# SCH_ledAndButonMcp23017_2023-08-30.net
KiCad netlist of a schematic drawn in EasyEDA
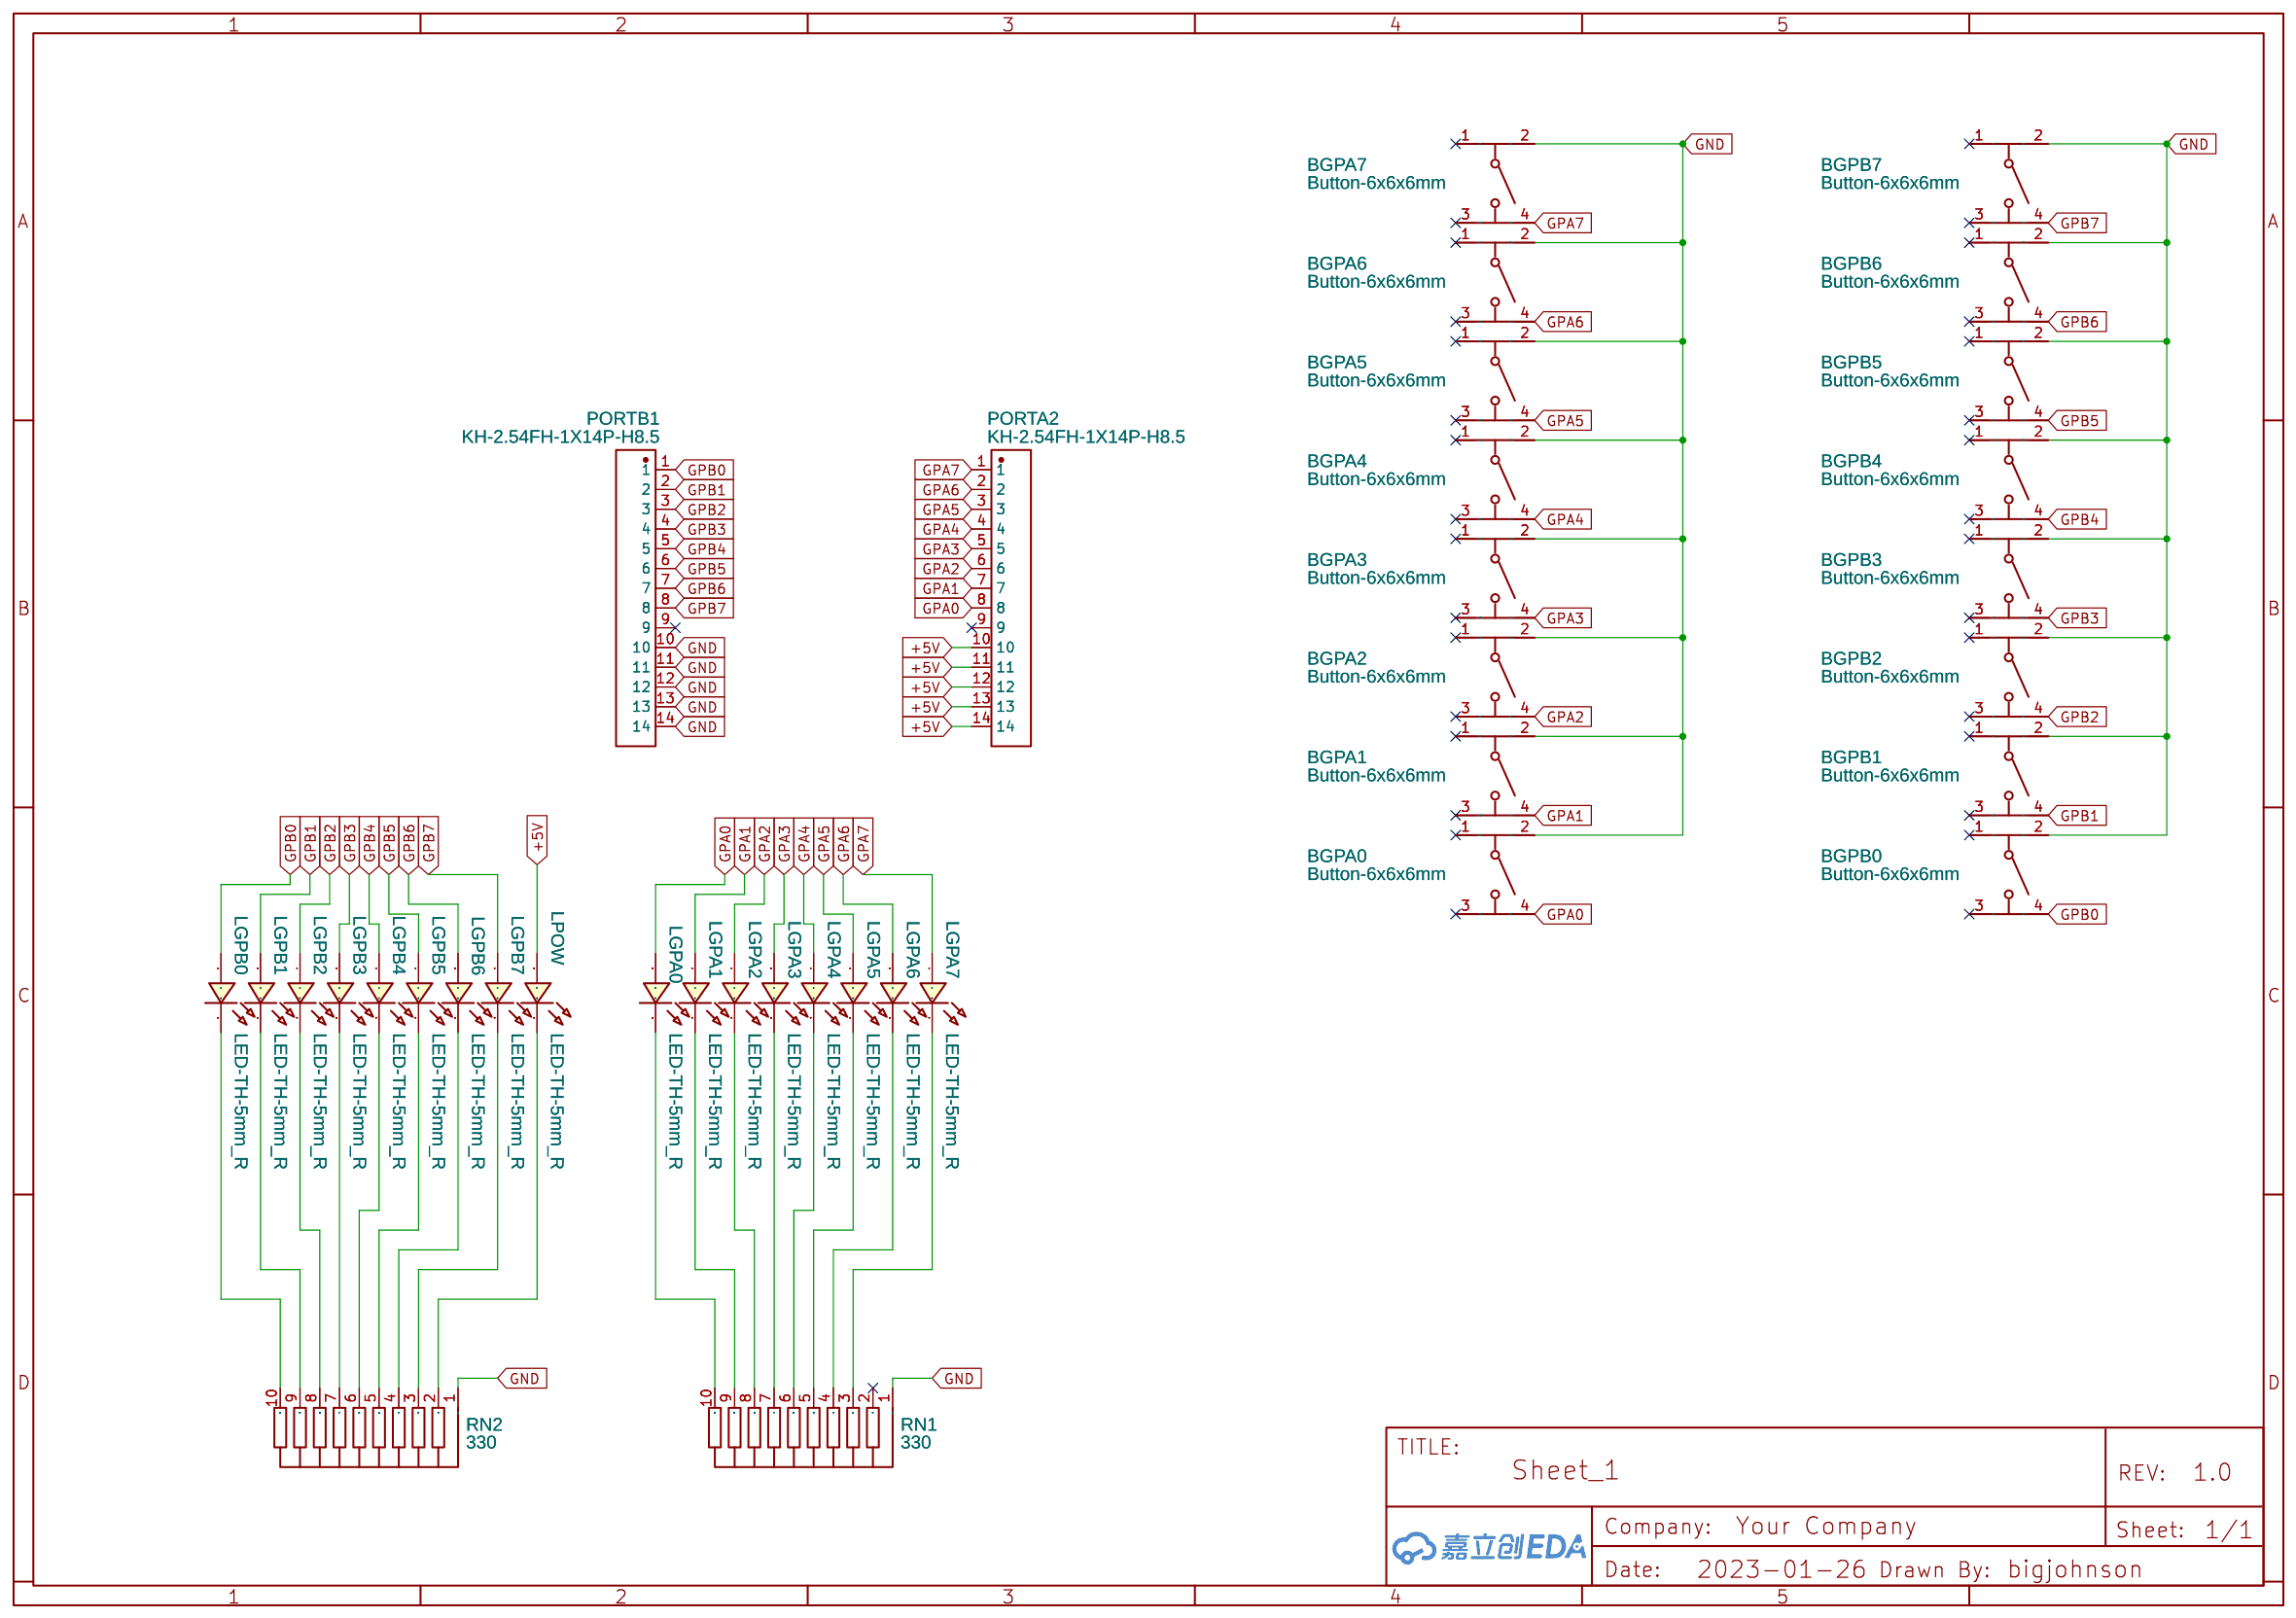
[diagram p0: schematic sheet]

(export (version "E")
  (design (tool "Eeschema 10.0.6"))
  (components
    (comp (ref "BGPA0")
      (value "Button-6x6x6mm")
      (fields
        (field (name "Manufacturer Part") "Switch,6*6*6Plastic head,260G, 0.25mm,Straight line")
        (field (name "Manufacturer") "BBJ")
      )
      (libsource (lib "") (part "Button-6x6x6mm_1"))
    )
    (comp (ref "BGPA1")
      (value "Button-6x6x6mm")
      (fields
        (field (name "Manufacturer Part") "Switch,6*6*6Plastic head,260G, 0.25mm,Straight line")
        (field (name "Manufacturer") "BBJ")
      )
      (libsource (lib "") (part "Button-6x6x6mm_1"))
    )
    (comp (ref "BGPA2")
      (value "Button-6x6x6mm")
      (fields
        (field (name "Manufacturer Part") "Switch,6*6*6Plastic head,260G, 0.25mm,Straight line")
        (field (name "Manufacturer") "BBJ")
      )
      (libsource (lib "") (part "Button-6x6x6mm_1"))
    )
    (comp (ref "BGPA3")
      (value "Button-6x6x6mm")
      (fields
        (field (name "Manufacturer Part") "Switch,6*6*6Plastic head,260G, 0.25mm,Straight line")
        (field (name "Manufacturer") "BBJ")
      )
      (libsource (lib "") (part "Button-6x6x6mm_1"))
    )
    (comp (ref "BGPA4")
      (value "Button-6x6x6mm")
      (fields
        (field (name "Manufacturer Part") "Switch,6*6*6Plastic head,260G, 0.25mm,Straight line")
        (field (name "Manufacturer") "BBJ")
      )
      (libsource (lib "") (part "Button-6x6x6mm_1"))
    )
    (comp (ref "BGPA5")
      (value "Button-6x6x6mm")
      (fields
        (field (name "Manufacturer Part") "Switch,6*6*6Plastic head,260G, 0.25mm,Straight line")
        (field (name "Manufacturer") "BBJ")
      )
      (libsource (lib "") (part "Button-6x6x6mm_1"))
    )
    (comp (ref "BGPA6")
      (value "Button-6x6x6mm")
      (fields
        (field (name "Manufacturer Part") "Switch,6*6*6Plastic head,260G, 0.25mm,Straight line")
        (field (name "Manufacturer") "BBJ")
      )
      (libsource (lib "") (part "Button-6x6x6mm_1"))
    )
    (comp (ref "BGPA7")
      (value "Button-6x6x6mm")
      (fields
        (field (name "Manufacturer Part") "Switch,6*6*6Plastic head,260G, 0.25mm,Straight line")
        (field (name "Manufacturer") "BBJ")
      )
      (libsource (lib "") (part "Button-6x6x6mm_1"))
    )
    (comp (ref "BGPB0")
      (value "Button-6x6x6mm")
      (fields
        (field (name "Manufacturer Part") "Switch,6*6*6Plastic head,260G, 0.25mm,Straight line")
        (field (name "Manufacturer") "BBJ")
      )
      (libsource (lib "") (part "Button-6x6x6mm"))
    )
    (comp (ref "BGPB1")
      (value "Button-6x6x6mm")
      (fields
        (field (name "Manufacturer Part") "Switch,6*6*6Plastic head,260G, 0.25mm,Straight line")
        (field (name "Manufacturer") "BBJ")
      )
      (libsource (lib "") (part "Button-6x6x6mm"))
    )
    (comp (ref "BGPB2")
      (value "Button-6x6x6mm")
      (fields
        (field (name "Manufacturer Part") "Switch,6*6*6Plastic head,260G, 0.25mm,Straight line")
        (field (name "Manufacturer") "BBJ")
      )
      (libsource (lib "") (part "Button-6x6x6mm"))
    )
    (comp (ref "BGPB3")
      (value "Button-6x6x6mm")
      (fields
        (field (name "Manufacturer Part") "Switch,6*6*6Plastic head,260G, 0.25mm,Straight line")
        (field (name "Manufacturer") "BBJ")
      )
      (libsource (lib "") (part "Button-6x6x6mm"))
    )
    (comp (ref "BGPB4")
      (value "Button-6x6x6mm")
      (fields
        (field (name "Manufacturer Part") "Switch,6*6*6Plastic head,260G, 0.25mm,Straight line")
        (field (name "Manufacturer") "BBJ")
      )
      (libsource (lib "") (part "Button-6x6x6mm"))
    )
    (comp (ref "BGPB5")
      (value "Button-6x6x6mm")
      (fields
        (field (name "Manufacturer Part") "Switch,6*6*6Plastic head,260G, 0.25mm,Straight line")
        (field (name "Manufacturer") "BBJ")
      )
      (libsource (lib "") (part "Button-6x6x6mm"))
    )
    (comp (ref "BGPB6")
      (value "Button-6x6x6mm")
      (fields
        (field (name "Manufacturer Part") "Switch,6*6*6Plastic head,260G, 0.25mm,Straight line")
        (field (name "Manufacturer") "BBJ")
      )
      (libsource (lib "") (part "Button-6x6x6mm"))
    )
    (comp (ref "BGPB7")
      (value "Button-6x6x6mm")
      (fields
        (field (name "Manufacturer Part") "Switch,6*6*6Plastic head,260G, 0.25mm,Straight line")
        (field (name "Manufacturer") "BBJ")
      )
      (libsource (lib "") (part "Button-6x6x6mm"))
    )
    (comp (ref "LGPA0")
      (value "LED-TH-5mm_R")
      (fields
        (field (name "Manufacturer Part") "333-2SURD/S530-A3")
        (field (name "Manufacturer") "EVERLIGHT(台湾亿光)")
      )
      (libsource (lib "") (part "LED-TH-5mm_R"))
    )
    (comp (ref "LGPA1")
      (value "LED-TH-5mm_R")
      (fields
        (field (name "Manufacturer Part") "333-2SURD/S530-A3")
        (field (name "Manufacturer") "EVERLIGHT(台湾亿光)")
      )
      (libsource (lib "") (part "LED-TH-5mm_R"))
    )
    (comp (ref "LGPA2")
      (value "LED-TH-5mm_R")
      (fields
        (field (name "Manufacturer Part") "333-2SURD/S530-A3")
        (field (name "Manufacturer") "EVERLIGHT(台湾亿光)")
      )
      (libsource (lib "") (part "LED-TH-5mm_R"))
    )
    (comp (ref "LGPA3")
      (value "LED-TH-5mm_R")
      (fields
        (field (name "Manufacturer Part") "333-2SURD/S530-A3")
        (field (name "Manufacturer") "EVERLIGHT(台湾亿光)")
      )
      (libsource (lib "") (part "LED-TH-5mm_R"))
    )
    (comp (ref "LGPA4")
      (value "LED-TH-5mm_R")
      (fields
        (field (name "Manufacturer Part") "333-2SURD/S530-A3")
        (field (name "Manufacturer") "EVERLIGHT(台湾亿光)")
      )
      (libsource (lib "") (part "LED-TH-5mm_R"))
    )
    (comp (ref "LGPA5")
      (value "LED-TH-5mm_R")
      (fields
        (field (name "Manufacturer Part") "333-2SURD/S530-A3")
        (field (name "Manufacturer") "EVERLIGHT(台湾亿光)")
      )
      (libsource (lib "") (part "LED-TH-5mm_R"))
    )
    (comp (ref "LGPA6")
      (value "LED-TH-5mm_R")
      (fields
        (field (name "Manufacturer Part") "333-2SURD/S530-A3")
        (field (name "Manufacturer") "EVERLIGHT(台湾亿光)")
      )
      (libsource (lib "") (part "LED-TH-5mm_R"))
    )
    (comp (ref "LGPA7")
      (value "LED-TH-5mm_R")
      (fields
        (field (name "Manufacturer Part") "333-2SURD/S530-A3")
        (field (name "Manufacturer") "EVERLIGHT(台湾亿光)")
      )
      (libsource (lib "") (part "LED-TH-5mm_R"))
    )
    (comp (ref "LGPB0")
      (value "LED-TH-5mm_R")
      (fields
        (field (name "Manufacturer Part") "333-2SURD/S530-A3")
        (field (name "Manufacturer") "EVERLIGHT(台湾亿光)")
      )
      (libsource (lib "") (part "LED-TH-5mm_R_1"))
    )
    (comp (ref "LGPB1")
      (value "LED-TH-5mm_R")
      (fields
        (field (name "Manufacturer Part") "333-2SURD/S530-A3")
        (field (name "Manufacturer") "EVERLIGHT(台湾亿光)")
      )
      (libsource (lib "") (part "LED-TH-5mm_R_1"))
    )
    (comp (ref "LGPB2")
      (value "LED-TH-5mm_R")
      (fields
        (field (name "Manufacturer Part") "333-2SURD/S530-A3")
        (field (name "Manufacturer") "EVERLIGHT(台湾亿光)")
      )
      (libsource (lib "") (part "LED-TH-5mm_R_1"))
    )
    (comp (ref "LGPB3")
      (value "LED-TH-5mm_R")
      (fields
        (field (name "Manufacturer Part") "333-2SURD/S530-A3")
        (field (name "Manufacturer") "EVERLIGHT(台湾亿光)")
      )
      (libsource (lib "") (part "LED-TH-5mm_R_1"))
    )
    (comp (ref "LGPB4")
      (value "LED-TH-5mm_R")
      (fields
        (field (name "Manufacturer Part") "333-2SURD/S530-A3")
        (field (name "Manufacturer") "EVERLIGHT(台湾亿光)")
      )
      (libsource (lib "") (part "LED-TH-5mm_R_1"))
    )
    (comp (ref "LGPB5")
      (value "LED-TH-5mm_R")
      (fields
        (field (name "Manufacturer Part") "333-2SURD/S530-A3")
        (field (name "Manufacturer") "EVERLIGHT(台湾亿光)")
      )
      (libsource (lib "") (part "LED-TH-5mm_R_1"))
    )
    (comp (ref "LGPB6")
      (value "LED-TH-5mm_R")
      (fields
        (field (name "Manufacturer Part") "333-2SURD/S530-A3")
        (field (name "Manufacturer") "EVERLIGHT(台湾亿光)")
      )
      (libsource (lib "") (part "LED-TH-5mm_R_1"))
    )
    (comp (ref "LGPB7")
      (value "LED-TH-5mm_R")
      (fields
        (field (name "Manufacturer Part") "333-2SURD/S530-A3")
        (field (name "Manufacturer") "EVERLIGHT(台湾亿光)")
      )
      (libsource (lib "") (part "LED-TH-5mm_R_1"))
    )
    (comp (ref "LPOW")
      (value "LED-TH-5mm_R")
      (fields
        (field (name "Manufacturer Part") "333-2SURD/S530-A3")
        (field (name "Manufacturer") "EVERLIGHT(台湾亿光)")
      )
      (libsource (lib "") (part "LED-TH-5mm_R_2"))
    )
    (comp (ref "PORTA2")
      (value "KH-2.54FH-1X14P-H8.5")
      (fields (field (name "Manufacturer") "kinghelm(金航标)"))
      (libsource (lib "") (part "KH-2.54FH-1X14P-H8.5_1"))
    )
    (comp (ref "PORTB1")
      (value "KH-2.54FH-1X14P-H8.5")
      (fields (field (name "Manufacturer") "kinghelm(金航标)"))
      (libsource (lib "") (part "KH-2.54FH-1X14P-H8.5"))
    )
    (comp (ref "RN1")
      (value "330")
      (fields
        (field (name "Manufacturer Part") "RAA10103G")
        (field (name "Manufacturer") "ZHUHAI MONEC ELEC")
      )
      (libsource (lib "") (part "RAA10103G"))
    )
    (comp (ref "RN2")
      (value "330")
      (fields
        (field (name "Manufacturer Part") "RAA10103G")
        (field (name "Manufacturer") "ZHUHAI MONEC ELEC")
      )
      (libsource (lib "") (part "RAA10103G"))
    )
  )
  (nets
    (net (code "1") (name "+5V") (class "Default")
      (node (ref "LPOW") (pin "1") (pinfunction "1_1") (pintype "unspecified"))
      (node (ref "PORTA2") (pin "10") (pinfunction "10_10") (pintype "unspecified"))
      (node (ref "PORTA2") (pin "11") (pinfunction "11_11") (pintype "unspecified"))
      (node (ref "PORTA2") (pin "12") (pinfunction "12_12") (pintype "unspecified"))
      (node (ref "PORTA2") (pin "13") (pinfunction "13_13") (pintype "unspecified"))
      (node (ref "PORTA2") (pin "14") (pinfunction "14_14") (pintype "unspecified"))
    )
    (net (code "2") (name "GND") (class "Default")
      (node (ref "BGPA0") (pin "2") (pinfunction "2_2") (pintype "unspecified"))
      (node (ref "BGPA1") (pin "2") (pinfunction "2_2") (pintype "unspecified"))
      (node (ref "BGPA2") (pin "2") (pinfunction "2_2") (pintype "unspecified"))
      (node (ref "BGPA3") (pin "2") (pinfunction "2_2") (pintype "unspecified"))
      (node (ref "BGPA4") (pin "2") (pinfunction "2_2") (pintype "unspecified"))
      (node (ref "BGPA5") (pin "2") (pinfunction "2_2") (pintype "unspecified"))
      (node (ref "BGPA6") (pin "2") (pinfunction "2_2") (pintype "unspecified"))
      (node (ref "BGPA7") (pin "2") (pinfunction "2_2") (pintype "unspecified"))
      (node (ref "BGPB0") (pin "2") (pinfunction "2_2") (pintype "unspecified"))
      (node (ref "BGPB1") (pin "2") (pinfunction "2_2") (pintype "unspecified"))
      (node (ref "BGPB2") (pin "2") (pinfunction "2_2") (pintype "unspecified"))
      (node (ref "BGPB3") (pin "2") (pinfunction "2_2") (pintype "unspecified"))
      (node (ref "BGPB4") (pin "2") (pinfunction "2_2") (pintype "unspecified"))
      (node (ref "BGPB5") (pin "2") (pinfunction "2_2") (pintype "unspecified"))
      (node (ref "BGPB6") (pin "2") (pinfunction "2_2") (pintype "unspecified"))
      (node (ref "BGPB7") (pin "2") (pinfunction "2_2") (pintype "unspecified"))
      (node (ref "PORTB1") (pin "10") (pinfunction "10_10") (pintype "unspecified"))
      (node (ref "PORTB1") (pin "11") (pinfunction "11_11") (pintype "unspecified"))
      (node (ref "PORTB1") (pin "12") (pinfunction "12_12") (pintype "unspecified"))
      (node (ref "PORTB1") (pin "13") (pinfunction "13_13") (pintype "unspecified"))
      (node (ref "PORTB1") (pin "14") (pinfunction "14_14") (pintype "unspecified"))
      (node (ref "RN1") (pin "1") (pinfunction "1_1") (pintype "unspecified"))
      (node (ref "RN2") (pin "1") (pinfunction "1_1") (pintype "unspecified"))
    )
    (net (code "3") (name "GPA0") (class "Default")
      (node (ref "BGPA0") (pin "4") (pinfunction "4_4") (pintype "unspecified"))
      (node (ref "LGPA0") (pin "1") (pinfunction "1_1") (pintype "unspecified"))
      (node (ref "PORTA2") (pin "8") (pinfunction "8_8") (pintype "unspecified"))
    )
    (net (code "4") (name "GPA1") (class "Default")
      (node (ref "BGPA1") (pin "4") (pinfunction "4_4") (pintype "unspecified"))
      (node (ref "LGPA1") (pin "1") (pinfunction "1_1") (pintype "unspecified"))
      (node (ref "PORTA2") (pin "7") (pinfunction "7_7") (pintype "unspecified"))
    )
    (net (code "5") (name "GPA2") (class "Default")
      (node (ref "BGPA2") (pin "4") (pinfunction "4_4") (pintype "unspecified"))
      (node (ref "LGPA2") (pin "1") (pinfunction "1_1") (pintype "unspecified"))
      (node (ref "PORTA2") (pin "6") (pinfunction "6_6") (pintype "unspecified"))
    )
    (net (code "6") (name "GPA3") (class "Default")
      (node (ref "BGPA3") (pin "4") (pinfunction "4_4") (pintype "unspecified"))
      (node (ref "LGPA3") (pin "1") (pinfunction "1_1") (pintype "unspecified"))
      (node (ref "PORTA2") (pin "5") (pinfunction "5_5") (pintype "unspecified"))
    )
    (net (code "7") (name "GPA4") (class "Default")
      (node (ref "BGPA4") (pin "4") (pinfunction "4_4") (pintype "unspecified"))
      (node (ref "LGPA4") (pin "1") (pinfunction "1_1") (pintype "unspecified"))
      (node (ref "PORTA2") (pin "4") (pinfunction "4_4") (pintype "unspecified"))
    )
    (net (code "8") (name "GPA5") (class "Default")
      (node (ref "BGPA5") (pin "4") (pinfunction "4_4") (pintype "unspecified"))
      (node (ref "LGPA5") (pin "1") (pinfunction "1_1") (pintype "unspecified"))
      (node (ref "PORTA2") (pin "3") (pinfunction "3_3") (pintype "unspecified"))
    )
    (net (code "9") (name "GPA6") (class "Default")
      (node (ref "BGPA6") (pin "4") (pinfunction "4_4") (pintype "unspecified"))
      (node (ref "LGPA6") (pin "1") (pinfunction "1_1") (pintype "unspecified"))
      (node (ref "PORTA2") (pin "2") (pinfunction "2_2") (pintype "unspecified"))
    )
    (net (code "10") (name "GPA7") (class "Default")
      (node (ref "BGPA7") (pin "4") (pinfunction "4_4") (pintype "unspecified"))
      (node (ref "LGPA7") (pin "1") (pinfunction "1_1") (pintype "unspecified"))
      (node (ref "PORTA2") (pin "1") (pinfunction "1_1") (pintype "unspecified"))
    )
    (net (code "11") (name "GPB0") (class "Default")
      (node (ref "BGPB0") (pin "4") (pinfunction "4_4") (pintype "unspecified"))
      (node (ref "LGPB0") (pin "1") (pinfunction "1_1") (pintype "unspecified"))
      (node (ref "PORTB1") (pin "1") (pinfunction "1_1") (pintype "unspecified"))
    )
    (net (code "12") (name "GPB1") (class "Default")
      (node (ref "BGPB1") (pin "4") (pinfunction "4_4") (pintype "unspecified"))
      (node (ref "LGPB1") (pin "1") (pinfunction "1_1") (pintype "unspecified"))
      (node (ref "PORTB1") (pin "2") (pinfunction "2_2") (pintype "unspecified"))
    )
    (net (code "13") (name "GPB2") (class "Default")
      (node (ref "BGPB2") (pin "4") (pinfunction "4_4") (pintype "unspecified"))
      (node (ref "LGPB2") (pin "1") (pinfunction "1_1") (pintype "unspecified"))
      (node (ref "PORTB1") (pin "3") (pinfunction "3_3") (pintype "unspecified"))
    )
    (net (code "14") (name "GPB3") (class "Default")
      (node (ref "BGPB3") (pin "4") (pinfunction "4_4") (pintype "unspecified"))
      (node (ref "LGPB3") (pin "1") (pinfunction "1_1") (pintype "unspecified"))
      (node (ref "PORTB1") (pin "4") (pinfunction "4_4") (pintype "unspecified"))
    )
    (net (code "15") (name "GPB4") (class "Default")
      (node (ref "BGPB4") (pin "4") (pinfunction "4_4") (pintype "unspecified"))
      (node (ref "LGPB4") (pin "1") (pinfunction "1_1") (pintype "unspecified"))
      (node (ref "PORTB1") (pin "5") (pinfunction "5_5") (pintype "unspecified"))
    )
    (net (code "16") (name "GPB5") (class "Default")
      (node (ref "BGPB5") (pin "4") (pinfunction "4_4") (pintype "unspecified"))
      (node (ref "LGPB5") (pin "1") (pinfunction "1_1") (pintype "unspecified"))
      (node (ref "PORTB1") (pin "6") (pinfunction "6_6") (pintype "unspecified"))
    )
    (net (code "17") (name "GPB6") (class "Default")
      (node (ref "BGPB6") (pin "4") (pinfunction "4_4") (pintype "unspecified"))
      (node (ref "LGPB6") (pin "1") (pinfunction "1_1") (pintype "unspecified"))
      (node (ref "PORTB1") (pin "7") (pinfunction "7_7") (pintype "unspecified"))
    )
    (net (code "18") (name "GPB7") (class "Default")
      (node (ref "BGPB7") (pin "4") (pinfunction "4_4") (pintype "unspecified"))
      (node (ref "LGPB7") (pin "1") (pinfunction "1_1") (pintype "unspecified"))
      (node (ref "PORTB1") (pin "8") (pinfunction "8_8") (pintype "unspecified"))
    )
    (net (code "19") (name "Net-(LGPA0-Pad2)") (class "Default")
      (node (ref "LGPA0") (pin "2") (pinfunction "2_2") (pintype "unspecified"))
      (node (ref "RN1") (pin "10") (pinfunction "10_10") (pintype "unspecified"))
    )
    (net (code "20") (name "Net-(LGPA1-Pad2)") (class "Default")
      (node (ref "LGPA1") (pin "2") (pinfunction "2_2") (pintype "unspecified"))
      (node (ref "RN1") (pin "9") (pinfunction "9_9") (pintype "unspecified"))
    )
    (net (code "21") (name "Net-(LGPA2-Pad2)") (class "Default")
      (node (ref "LGPA2") (pin "2") (pinfunction "2_2") (pintype "unspecified"))
      (node (ref "RN1") (pin "8") (pinfunction "8_8") (pintype "unspecified"))
    )
    (net (code "22") (name "Net-(LGPA3-Pad2)") (class "Default")
      (node (ref "LGPA3") (pin "2") (pinfunction "2_2") (pintype "unspecified"))
      (node (ref "RN1") (pin "7") (pinfunction "7_7") (pintype "unspecified"))
    )
    (net (code "23") (name "Net-(LGPA4-Pad2)") (class "Default")
      (node (ref "LGPA4") (pin "2") (pinfunction "2_2") (pintype "unspecified"))
      (node (ref "RN1") (pin "6") (pinfunction "6_6") (pintype "unspecified"))
    )
    (net (code "24") (name "Net-(LGPA5-Pad2)") (class "Default")
      (node (ref "LGPA5") (pin "2") (pinfunction "2_2") (pintype "unspecified"))
      (node (ref "RN1") (pin "5") (pinfunction "5_5") (pintype "unspecified"))
    )
    (net (code "25") (name "Net-(LGPA6-Pad2)") (class "Default")
      (node (ref "LGPA6") (pin "2") (pinfunction "2_2") (pintype "unspecified"))
      (node (ref "RN1") (pin "4") (pinfunction "4_4") (pintype "unspecified"))
    )
    (net (code "26") (name "Net-(LGPA7-Pad2)") (class "Default")
      (node (ref "LGPA7") (pin "2") (pinfunction "2_2") (pintype "unspecified"))
      (node (ref "RN1") (pin "3") (pinfunction "3_3") (pintype "unspecified"))
    )
    (net (code "27") (name "Net-(LGPB0-Pad2)") (class "Default")
      (node (ref "LGPB0") (pin "2") (pinfunction "2_2") (pintype "unspecified"))
      (node (ref "RN2") (pin "10") (pinfunction "10_10") (pintype "unspecified"))
    )
    (net (code "28") (name "Net-(LGPB1-Pad2)") (class "Default")
      (node (ref "LGPB1") (pin "2") (pinfunction "2_2") (pintype "unspecified"))
      (node (ref "RN2") (pin "9") (pinfunction "9_9") (pintype "unspecified"))
    )
    (net (code "29") (name "Net-(LGPB2-Pad2)") (class "Default")
      (node (ref "LGPB2") (pin "2") (pinfunction "2_2") (pintype "unspecified"))
      (node (ref "RN2") (pin "8") (pinfunction "8_8") (pintype "unspecified"))
    )
    (net (code "30") (name "Net-(LGPB3-Pad2)") (class "Default")
      (node (ref "LGPB3") (pin "2") (pinfunction "2_2") (pintype "unspecified"))
      (node (ref "RN2") (pin "7") (pinfunction "7_7") (pintype "unspecified"))
    )
    (net (code "31") (name "Net-(LGPB4-Pad2)") (class "Default")
      (node (ref "LGPB4") (pin "2") (pinfunction "2_2") (pintype "unspecified"))
      (node (ref "RN2") (pin "6") (pinfunction "6_6") (pintype "unspecified"))
    )
    (net (code "32") (name "Net-(LGPB5-Pad2)") (class "Default")
      (node (ref "LGPB5") (pin "2") (pinfunction "2_2") (pintype "unspecified"))
      (node (ref "RN2") (pin "5") (pinfunction "5_5") (pintype "unspecified"))
    )
    (net (code "33") (name "Net-(LGPB6-Pad2)") (class "Default")
      (node (ref "LGPB6") (pin "2") (pinfunction "2_2") (pintype "unspecified"))
      (node (ref "RN2") (pin "4") (pinfunction "4_4") (pintype "unspecified"))
    )
    (net (code "34") (name "Net-(LGPB7-Pad2)") (class "Default")
      (node (ref "LGPB7") (pin "2") (pinfunction "2_2") (pintype "unspecified"))
      (node (ref "RN2") (pin "3") (pinfunction "3_3") (pintype "unspecified"))
    )
    (net (code "35") (name "Net-(LPOW-Pad2)") (class "Default")
      (node (ref "LPOW") (pin "2") (pinfunction "2_2") (pintype "unspecified"))
      (node (ref "RN2") (pin "2") (pinfunction "2_2") (pintype "unspecified"))
    )
    (net (code "36") (name "unconnected-(BGPA0-Pad1)") (class "Default")
      (node (ref "BGPA0") (pin "1") (pinfunction "1_1") (pintype "unspecified+no_connect"))
    )
    (net (code "37") (name "unconnected-(BGPA0-Pad3)") (class "Default")
      (node (ref "BGPA0") (pin "3") (pinfunction "3_3") (pintype "unspecified+no_connect"))
    )
    (net (code "38") (name "unconnected-(BGPA1-Pad1)") (class "Default")
      (node (ref "BGPA1") (pin "1") (pinfunction "1_1") (pintype "unspecified+no_connect"))
    )
    (net (code "39") (name "unconnected-(BGPA1-Pad3)") (class "Default")
      (node (ref "BGPA1") (pin "3") (pinfunction "3_3") (pintype "unspecified+no_connect"))
    )
    (net (code "40") (name "unconnected-(BGPA2-Pad1)") (class "Default")
      (node (ref "BGPA2") (pin "1") (pinfunction "1_1") (pintype "unspecified+no_connect"))
    )
    (net (code "41") (name "unconnected-(BGPA2-Pad3)") (class "Default")
      (node (ref "BGPA2") (pin "3") (pinfunction "3_3") (pintype "unspecified+no_connect"))
    )
    (net (code "42") (name "unconnected-(BGPA3-Pad1)") (class "Default")
      (node (ref "BGPA3") (pin "1") (pinfunction "1_1") (pintype "unspecified+no_connect"))
    )
    (net (code "43") (name "unconnected-(BGPA3-Pad3)") (class "Default")
      (node (ref "BGPA3") (pin "3") (pinfunction "3_3") (pintype "unspecified+no_connect"))
    )
    (net (code "44") (name "unconnected-(BGPA4-Pad1)") (class "Default")
      (node (ref "BGPA4") (pin "1") (pinfunction "1_1") (pintype "unspecified+no_connect"))
    )
    (net (code "45") (name "unconnected-(BGPA4-Pad3)") (class "Default")
      (node (ref "BGPA4") (pin "3") (pinfunction "3_3") (pintype "unspecified+no_connect"))
    )
    (net (code "46") (name "unconnected-(BGPA5-Pad1)") (class "Default")
      (node (ref "BGPA5") (pin "1") (pinfunction "1_1") (pintype "unspecified+no_connect"))
    )
    (net (code "47") (name "unconnected-(BGPA5-Pad3)") (class "Default")
      (node (ref "BGPA5") (pin "3") (pinfunction "3_3") (pintype "unspecified+no_connect"))
    )
    (net (code "48") (name "unconnected-(BGPA6-Pad1)") (class "Default")
      (node (ref "BGPA6") (pin "1") (pinfunction "1_1") (pintype "unspecified+no_connect"))
    )
    (net (code "49") (name "unconnected-(BGPA6-Pad3)") (class "Default")
      (node (ref "BGPA6") (pin "3") (pinfunction "3_3") (pintype "unspecified+no_connect"))
    )
    (net (code "50") (name "unconnected-(BGPA7-Pad1)") (class "Default")
      (node (ref "BGPA7") (pin "1") (pinfunction "1_1") (pintype "unspecified+no_connect"))
    )
    (net (code "51") (name "unconnected-(BGPA7-Pad3)") (class "Default")
      (node (ref "BGPA7") (pin "3") (pinfunction "3_3") (pintype "unspecified+no_connect"))
    )
    (net (code "52") (name "unconnected-(BGPB0-Pad1)") (class "Default")
      (node (ref "BGPB0") (pin "1") (pinfunction "1_1") (pintype "unspecified+no_connect"))
    )
    (net (code "53") (name "unconnected-(BGPB0-Pad3)") (class "Default")
      (node (ref "BGPB0") (pin "3") (pinfunction "3_3") (pintype "unspecified+no_connect"))
    )
    (net (code "54") (name "unconnected-(BGPB1-Pad1)") (class "Default")
      (node (ref "BGPB1") (pin "1") (pinfunction "1_1") (pintype "unspecified+no_connect"))
    )
    (net (code "55") (name "unconnected-(BGPB1-Pad3)") (class "Default")
      (node (ref "BGPB1") (pin "3") (pinfunction "3_3") (pintype "unspecified+no_connect"))
    )
    (net (code "56") (name "unconnected-(BGPB2-Pad1)") (class "Default")
      (node (ref "BGPB2") (pin "1") (pinfunction "1_1") (pintype "unspecified+no_connect"))
    )
    (net (code "57") (name "unconnected-(BGPB2-Pad3)") (class "Default")
      (node (ref "BGPB2") (pin "3") (pinfunction "3_3") (pintype "unspecified+no_connect"))
    )
    (net (code "58") (name "unconnected-(BGPB3-Pad1)") (class "Default")
      (node (ref "BGPB3") (pin "1") (pinfunction "1_1") (pintype "unspecified+no_connect"))
    )
    (net (code "59") (name "unconnected-(BGPB3-Pad3)") (class "Default")
      (node (ref "BGPB3") (pin "3") (pinfunction "3_3") (pintype "unspecified+no_connect"))
    )
    (net (code "60") (name "unconnected-(BGPB4-Pad1)") (class "Default")
      (node (ref "BGPB4") (pin "1") (pinfunction "1_1") (pintype "unspecified+no_connect"))
    )
    (net (code "61") (name "unconnected-(BGPB4-Pad3)") (class "Default")
      (node (ref "BGPB4") (pin "3") (pinfunction "3_3") (pintype "unspecified+no_connect"))
    )
    (net (code "62") (name "unconnected-(BGPB5-Pad1)") (class "Default")
      (node (ref "BGPB5") (pin "1") (pinfunction "1_1") (pintype "unspecified+no_connect"))
    )
    (net (code "63") (name "unconnected-(BGPB5-Pad3)") (class "Default")
      (node (ref "BGPB5") (pin "3") (pinfunction "3_3") (pintype "unspecified+no_connect"))
    )
    (net (code "64") (name "unconnected-(BGPB6-Pad1)") (class "Default")
      (node (ref "BGPB6") (pin "1") (pinfunction "1_1") (pintype "unspecified+no_connect"))
    )
    (net (code "65") (name "unconnected-(BGPB6-Pad3)") (class "Default")
      (node (ref "BGPB6") (pin "3") (pinfunction "3_3") (pintype "unspecified+no_connect"))
    )
    (net (code "66") (name "unconnected-(BGPB7-Pad1)") (class "Default")
      (node (ref "BGPB7") (pin "1") (pinfunction "1_1") (pintype "unspecified+no_connect"))
    )
    (net (code "67") (name "unconnected-(BGPB7-Pad3)") (class "Default")
      (node (ref "BGPB7") (pin "3") (pinfunction "3_3") (pintype "unspecified+no_connect"))
    )
    (net (code "68") (name "unconnected-(PORTA2-Pad9)") (class "Default")
      (node (ref "PORTA2") (pin "9") (pinfunction "9_9") (pintype "unspecified+no_connect"))
    )
    (net (code "69") (name "unconnected-(PORTB1-Pad9)") (class "Default")
      (node (ref "PORTB1") (pin "9") (pinfunction "9_9") (pintype "unspecified+no_connect"))
    )
    (net (code "70") (name "unconnected-(RN1-Pad2)") (class "Default")
      (node (ref "RN1") (pin "2") (pinfunction "2_2") (pintype "unspecified+no_connect"))
    )
  )
)
